# LIC_Rack_BB-01_ext.net
KiCad netlist of a schematic drawn in EAGLE
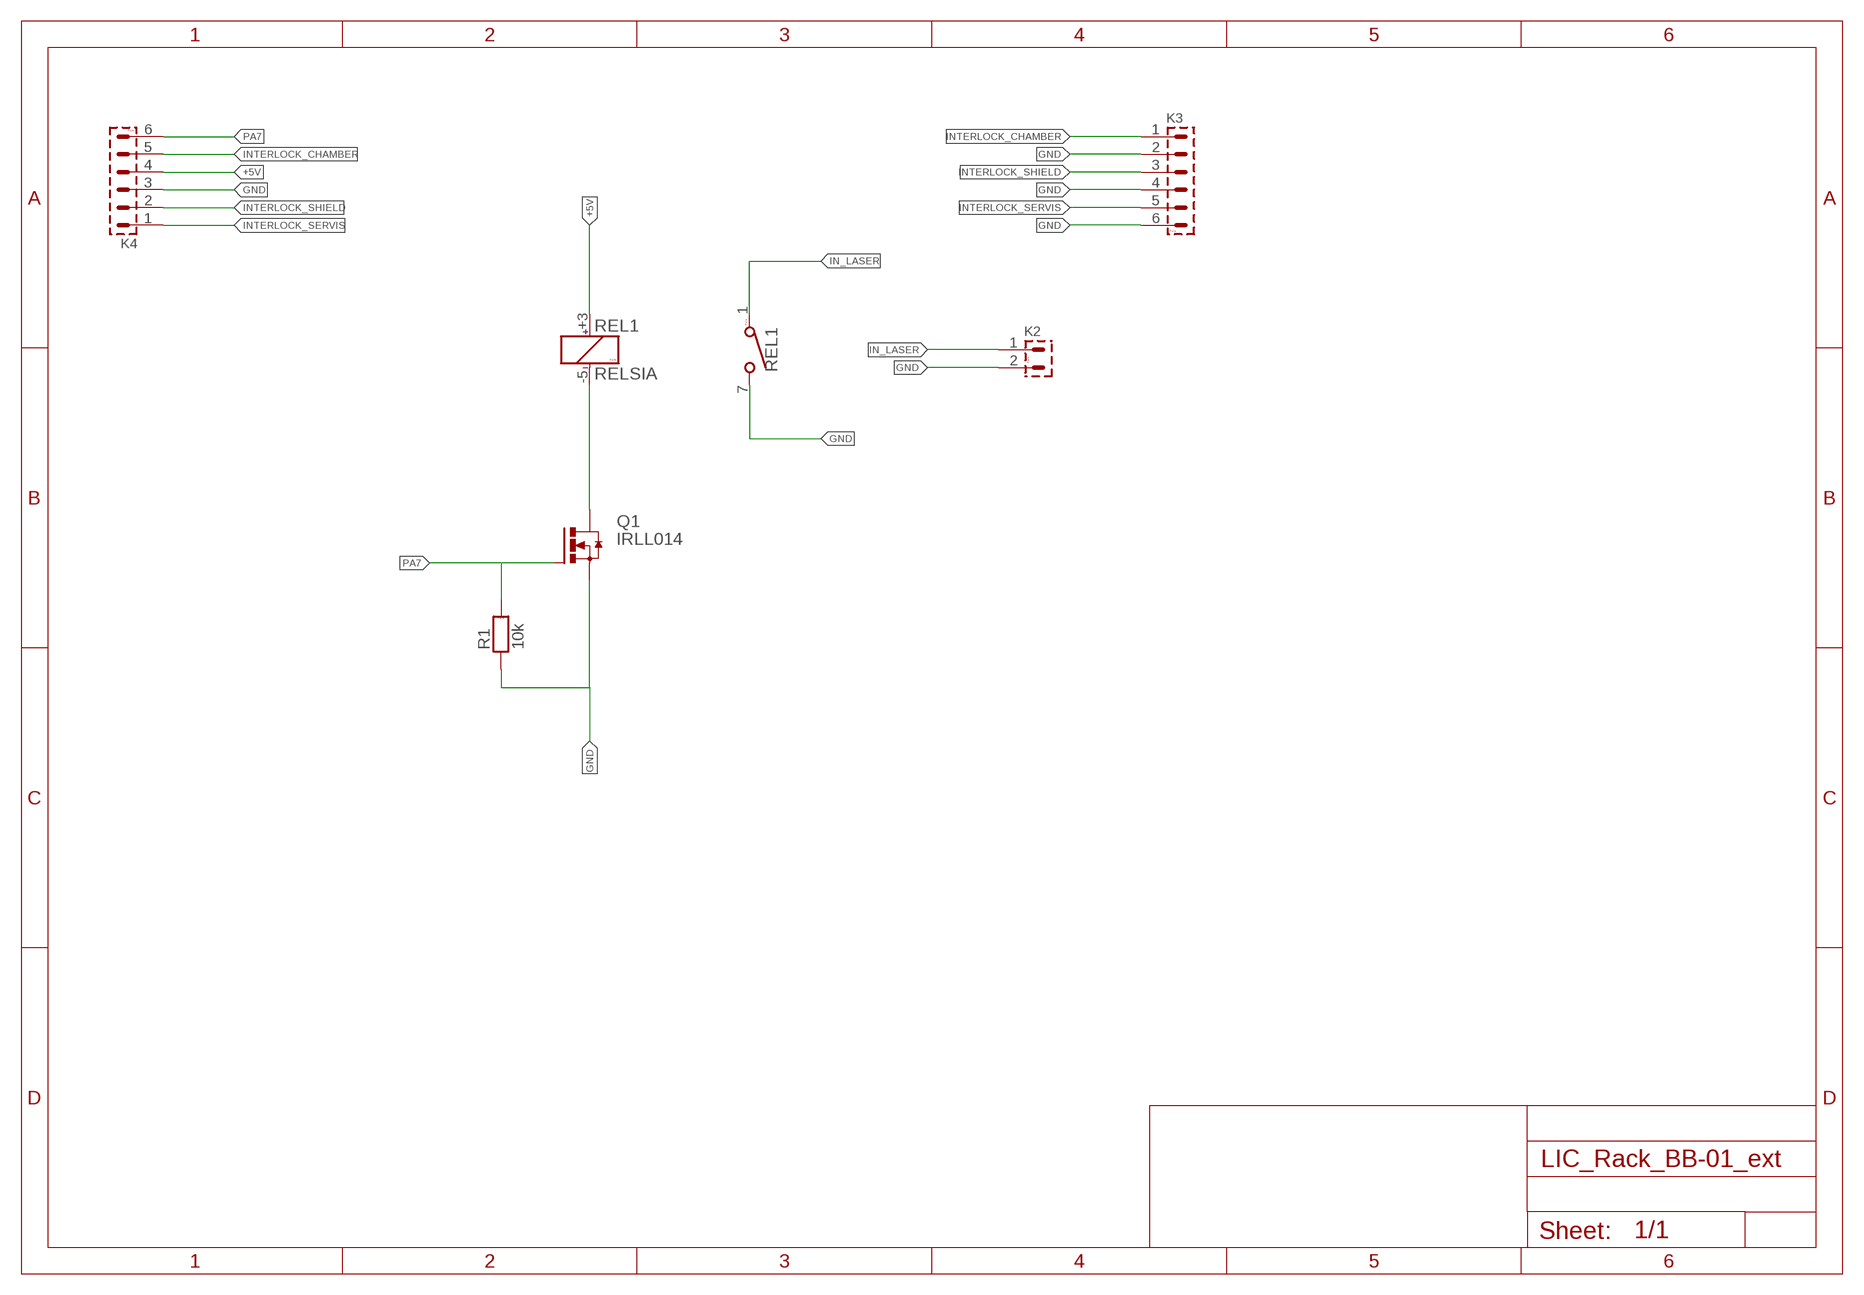
[diagram p0: schematic, sheet 1]

(export (version "E")
  (design (tool "Eeschema 10.0.6"))
  (components
    (comp (ref "K2")
      (value "PSH02-02W")
      (footprint "eagle-import:PSH02-02W")
      (libsource (lib "eagle-import") (part "PSH02-02W"))
    )
    (comp (ref "K3")
      (value "PSH02-06W")
      (footprint "eagle-import:PSH02-06W")
      (libsource (lib "eagle-import") (part "PSH02-06W"))
    )
    (comp (ref "K4")
      (value "PSH02-06W")
      (footprint "eagle-import:PSH02-06W")
      (libsource (lib "eagle-import") (part "PSH02-06W"))
    )
    (comp (ref "Q1")
      (value "IRLL014")
      (footprint "eagle-import:SOT223")
      (libsource (lib "eagle-import") (part "N-HEXFET-2D_?-SOT232"))
    )
    (comp (ref "R1")
      (value "10k")
      (footprint "eagle-import:1206")
      (libsource (lib "eagle-import") (part "R_1206"))
    )
    (comp (ref "REL1")
      (value "RELSIA")
      (footprint "eagle-import:RELSIA")
      (libsource (lib "eagle-import") (part "RELSIA??"))
    )
  )
  (nets
    (net (code "1") (name "+5V") (class "Default")
      (node (ref "K4") (pin "4") (pinfunction "4_4") (pintype "passive"))
      (node (ref "REL1") (pin "+3") (pinfunction "C+_+3") (pintype "passive"))
    )
    (net (code "2") (name "GND") (class "Default")
      (node (ref "K2") (pin "2") (pinfunction "2_2") (pintype "passive"))
      (node (ref "K3") (pin "2") (pinfunction "2_2") (pintype "passive"))
      (node (ref "K3") (pin "4") (pinfunction "4_4") (pintype "passive"))
      (node (ref "K3") (pin "6") (pinfunction "6_6") (pintype "passive"))
      (node (ref "K4") (pin "3") (pinfunction "3_3") (pintype "passive"))
      (node (ref "Q1") (pin "3") (pinfunction "S_3") (pintype "passive"))
      (node (ref "R1") (pin "1") (pinfunction "1_1") (pintype "passive"))
      (node (ref "REL1") (pin "7") (pinfunction "2_7") (pintype "passive"))
    )
    (net (code "3") (name "INTERLOCK_CHAMBER") (class "Default")
      (node (ref "K3") (pin "1") (pinfunction "1_1") (pintype "passive"))
      (node (ref "K4") (pin "5") (pinfunction "5_5") (pintype "passive"))
    )
    (net (code "4") (name "INTERLOCK_SERVIS") (class "Default")
      (node (ref "K3") (pin "5") (pinfunction "5_5") (pintype "passive"))
      (node (ref "K4") (pin "1") (pinfunction "1_1") (pintype "passive"))
    )
    (net (code "5") (name "INTERLOCK_SHIELD") (class "Default")
      (node (ref "K3") (pin "3") (pinfunction "3_3") (pintype "passive"))
      (node (ref "K4") (pin "2") (pinfunction "2_2") (pintype "passive"))
    )
    (net (code "6") (name "IN_LASER") (class "Default")
      (node (ref "K2") (pin "1") (pinfunction "1_1") (pintype "passive"))
      (node (ref "REL1") (pin "1") (pinfunction "1_1") (pintype "passive"))
    )
    (net (code "7") (name "Net-(REL1A-C-)") (class "Default")
      (node (ref "Q1") (pin "2") (pinfunction "D_2") (pintype "passive"))
      (node (ref "Q1") (pin "4") (pinfunction "D_4") (pintype "passive"))
      (node (ref "REL1") (pin "-5") (pinfunction "C-_-5") (pintype "passive"))
    )
    (net (code "8") (name "PA7") (class "Default")
      (node (ref "K4") (pin "6") (pinfunction "6_6") (pintype "passive"))
      (node (ref "Q1") (pin "1") (pinfunction "G_1") (pintype "passive"))
      (node (ref "R1") (pin "2") (pinfunction "2_2") (pintype "passive"))
    )
  )
)
